# subckt_Attenuator_HMC539ALP3.net
KiCad netlist of a schematic drawn in Altium Designer
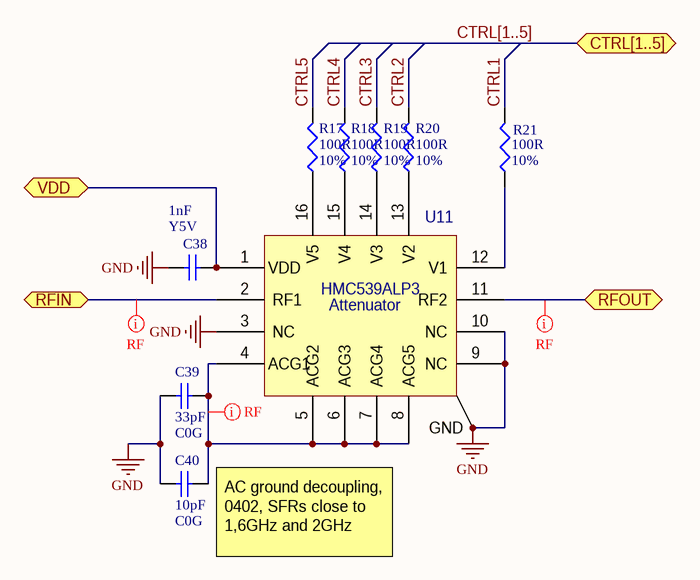
[diagram p0: subckt_Attenuator_HMC539ALP3.SchDoc]

(export (version "E")
  (design (tool "Eeschema 10.0.6"))
  (components
    (comp (ref "C38")
      (value "1nF")
      (footprint "CAP0603")
      (description "Capacitor")
      (fields (field (name "DIELECTRIC") "Y5V"))
      (libsource (lib "lib_basic") (part "Capacitor"))
    )
    (comp (ref "C39")
      (value "33pF")
      (footprint "Model Name")
      (description "Capacitor")
      (fields (field (name "DIELECTRIC") "C0G"))
      (libsource (lib "lib_basic") (part "Capacitor"))
    )
    (comp (ref "C40")
      (value "10pF")
      (footprint "Model Name")
      (description "Capacitor")
      (fields (field (name "DIELECTRIC") "C0G"))
      (libsource (lib "lib_basic") (part "Capacitor"))
    )
    (comp (ref "R17")
      (value "100R")
      (footprint "RES0603")
      (description "Resistor")
      (fields (field (name "TYPE") "10%"))
      (libsource (lib "lib_basic") (part "Resistor"))
    )
    (comp (ref "R18")
      (value "100R")
      (footprint "RES0603")
      (description "Resistor")
      (fields (field (name "TYPE") "10%"))
      (libsource (lib "lib_basic") (part "Resistor"))
    )
    (comp (ref "R19")
      (value "100R")
      (footprint "RES0603")
      (description "Resistor")
      (fields (field (name "TYPE") "10%"))
      (libsource (lib "lib_basic") (part "Resistor"))
    )
    (comp (ref "R20")
      (value "100R")
      (footprint "RES0603")
      (description "Resistor")
      (fields (field (name "TYPE") "10%"))
      (libsource (lib "lib_basic") (part "Resistor"))
    )
    (comp (ref "R21")
      (value "100R")
      (footprint "RES0603")
      (description "Resistor")
      (fields (field (name "TYPE") "10%"))
      (libsource (lib "lib_basic") (part "Resistor"))
    )
    (comp (ref "U11")
      (value "HMC539ALP3")
      (description "Attenuator 7.75dB, DC-4GHz, 0.25dB LSB")
      (libsource (lib "lib_RF_passives") (part "AD_HMC539ALP3"))
    )
  )
  (nets
    (net (code "1") (name "/CTRL1") (class "Default")
      (node (ref "R21") (pin "2") (pinfunction "2_2") (pintype "passive"))
    )
    (net (code "2") (name "/CTRL2") (class "Default")
      (node (ref "R20") (pin "2") (pinfunction "2_2") (pintype "passive"))
    )
    (net (code "3") (name "/CTRL3") (class "Default")
      (node (ref "R19") (pin "2") (pinfunction "2_2") (pintype "passive"))
    )
    (net (code "4") (name "/CTRL4") (class "Default")
      (node (ref "R18") (pin "2") (pinfunction "2_2") (pintype "passive"))
    )
    (net (code "5") (name "/CTRL5") (class "Default")
      (node (ref "R17") (pin "2") (pinfunction "2_2") (pintype "passive"))
    )
    (net (code "7") (name "/RFIN") (class "Default")
      (node (ref "U11") (pin "2") (pinfunction "RF1_2") (pintype "passive"))
    )
    (net (code "8") (name "/RFOUT") (class "Default")
      (node (ref "U11") (pin "11") (pinfunction "RF2_11") (pintype "passive"))
    )
    (net (code "9") (name "/VDD") (class "Default")
      (node (ref "C38") (pin "1") (pinfunction "1_1") (pintype "passive"))
      (node (ref "U11") (pin "1") (pinfunction "VDD_1") (pintype "passive"))
    )
    (net (code "10") (name "GND") (class "Default")
      (node (ref "C38") (pin "2") (pinfunction "2_2") (pintype "passive"))
      (node (ref "C39") (pin "1") (pinfunction "1_1") (pintype "passive"))
      (node (ref "C40") (pin "1") (pinfunction "1_1") (pintype "passive"))
      (node (ref "U11") (pin "10") (pinfunction "NC_10") (pintype "passive"))
      (node (ref "U11") (pin "17") (pinfunction "GND_17") (pintype "passive"))
      (node (ref "U11") (pin "3") (pinfunction "NC_3") (pintype "passive"))
      (node (ref "U11") (pin "9") (pinfunction "NC_9") (pintype "passive"))
    )
    (net (code "11") (name "Net-(U11-ACG1)") (class "Default")
      (node (ref "C39") (pin "2") (pinfunction "2_2") (pintype "passive"))
      (node (ref "C40") (pin "2") (pinfunction "2_2") (pintype "passive"))
      (node (ref "U11") (pin "4") (pinfunction "ACG1_4") (pintype "passive"))
      (node (ref "U11") (pin "5") (pinfunction "ACG2_5") (pintype "passive"))
      (node (ref "U11") (pin "6") (pinfunction "ACG3_6") (pintype "passive"))
      (node (ref "U11") (pin "7") (pinfunction "ACG4_7") (pintype "passive"))
      (node (ref "U11") (pin "8") (pinfunction "ACG5_8") (pintype "passive"))
    )
    (net (code "12") (name "Net-(U11-V1)") (class "Default")
      (node (ref "R21") (pin "1") (pinfunction "1_1") (pintype "passive"))
      (node (ref "U11") (pin "12") (pinfunction "V1_12") (pintype "passive"))
    )
    (net (code "13") (name "Net-(U11-V2)") (class "Default")
      (node (ref "R20") (pin "1") (pinfunction "1_1") (pintype "passive"))
      (node (ref "U11") (pin "13") (pinfunction "V2_13") (pintype "passive"))
    )
    (net (code "14") (name "Net-(U11-V3)") (class "Default")
      (node (ref "R19") (pin "1") (pinfunction "1_1") (pintype "passive"))
      (node (ref "U11") (pin "14") (pinfunction "V3_14") (pintype "passive"))
    )
    (net (code "15") (name "Net-(U11-V4)") (class "Default")
      (node (ref "R18") (pin "1") (pinfunction "1_1") (pintype "passive"))
      (node (ref "U11") (pin "15") (pinfunction "V4_15") (pintype "passive"))
    )
    (net (code "16") (name "Net-(U11-V5)") (class "Default")
      (node (ref "R17") (pin "1") (pinfunction "1_1") (pintype "passive"))
      (node (ref "U11") (pin "16") (pinfunction "V5_16") (pintype "passive"))
    )
  )
)
